# RSeries_VCSensor_v1_2.net
KiCad netlist of a schematic drawn in EAGLE
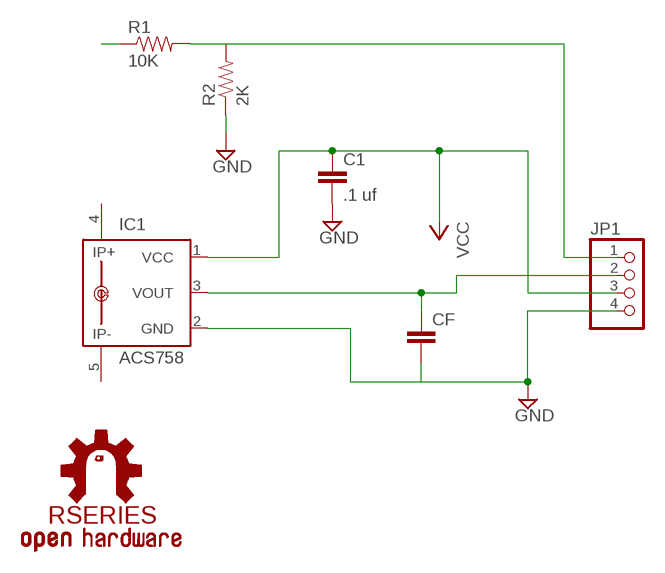
[diagram p0: schematic, sheet 1]

(export (version "E")
  (design (tool "Eeschema 10.0.6"))
  (components
    (comp (ref "C1")
      (value ".1 uf")
      (footprint "eagle-import:CAP-PTH-SMALL")
      (libsource (lib "eagle-import") (part "CAPPTH"))
    )
    (comp (ref "CF")
      (value "CAPPTH1")
      (footprint "eagle-import:CAP-PTH-5MM")
      (libsource (lib "eagle-import") (part "CAPPTH1"))
    )
    (comp (ref "IC1")
      (value "ACS758")
      (footprint "eagle-import:CB-PFF")
      (fields (field (name "MPN") "ACS758LCB-050B-PFF-T"))
      (libsource (lib "eagle-import") (part "ACS758LCB-050B-PFF-T"))
    )
    (comp (ref "JP1")
      (value "PINHD-1X4")
      (footprint "eagle-import:1X04")
      (libsource (lib "eagle-import") (part "PINHD-1X4"))
    )
    (comp (ref "R1")
      (value "10K")
      (footprint "eagle-import:AXIAL-0.4")
      (libsource (lib "eagle-import") (part "RESISTORPTH-1/4W"))
    )
    (comp (ref "R2")
      (value "2K")
      (footprint "eagle-import:AXIAL-0.4")
      (libsource (lib "eagle-import") (part "RESISTORPTH-1/4W"))
    )
    (comp (ref "U$1")
      (value "RSERIES-OSHW-LOGO")
      (footprint "eagle-import:RSERIES-OSHW-LOGO-LARGE")
      (libsource (lib "eagle-import") (part "RSERIES-OSHW-LOGO"))
    )
  )
  (nets
    (net (code "1") (name "GND") (class "Default")
      (node (ref "C1") (pin "2") (pinfunction "2_2") (pintype "passive"))
      (node (ref "CF") (pin "2") (pinfunction "2_2") (pintype "passive"))
      (node (ref "IC1") (pin "2") (pinfunction "GND_2") (pintype "power_in"))
      (node (ref "JP1") (pin "4") (pinfunction "4_4") (pintype "passive"))
      (node (ref "R2") (pin "P$1") (pinfunction "1_P$1") (pintype "passive"))
    )
    (net (code "2") (name "Net-(IC1-VOUT)") (class "Default")
      (node (ref "CF") (pin "1") (pinfunction "1_1") (pintype "passive"))
      (node (ref "IC1") (pin "3") (pinfunction "VOUT_3") (pintype "output"))
      (node (ref "JP1") (pin "2") (pinfunction "2_2") (pintype "passive"))
    )
    (net (code "3") (name "Net-(R1-2)") (class "Default")
      (node (ref "JP1") (pin "1") (pinfunction "1_1") (pintype "passive"))
      (node (ref "R1") (pin "P$2") (pinfunction "2_P$2") (pintype "passive"))
      (node (ref "R2") (pin "P$2") (pinfunction "2_P$2") (pintype "passive"))
    )
    (net (code "4") (name "VCC") (class "Default")
      (node (ref "C1") (pin "1") (pinfunction "1_1") (pintype "passive"))
      (node (ref "IC1") (pin "1") (pinfunction "VCC_1") (pintype "power_in"))
      (node (ref "JP1") (pin "3") (pinfunction "3_3") (pintype "passive"))
    )
    (net (code "5") (name "unconnected-(IC1-IP+-Pad4)") (class "Default")
      (node (ref "IC1") (pin "4") (pinfunction "IP+_4") (pintype "passive"))
    )
    (net (code "6") (name "unconnected-(IC1-IP--Pad5)") (class "Default")
      (node (ref "IC1") (pin "5") (pinfunction "IP-_5") (pintype "passive"))
    )
    (net (code "7") (name "unconnected-(IC1-PadIP+1)") (class "Default")
      (node (ref "IC1") (pin "IP+1") (pinfunction "IP+1_IP+1") (pintype "input"))
    )
    (net (code "8") (name "unconnected-(IC1-PadIP-1)") (class "Default")
      (node (ref "IC1") (pin "IP-1") (pinfunction "IP-1_IP-1") (pintype "input"))
    )
    (net (code "9") (name "unconnected-(R1-1-PadP$1)") (class "Default")
      (node (ref "R1") (pin "P$1") (pinfunction "1_P$1") (pintype "passive"))
    )
  )
)
